# LEDpaideng.net
KiCad netlist of a schematic drawn in EasyEDA Pro
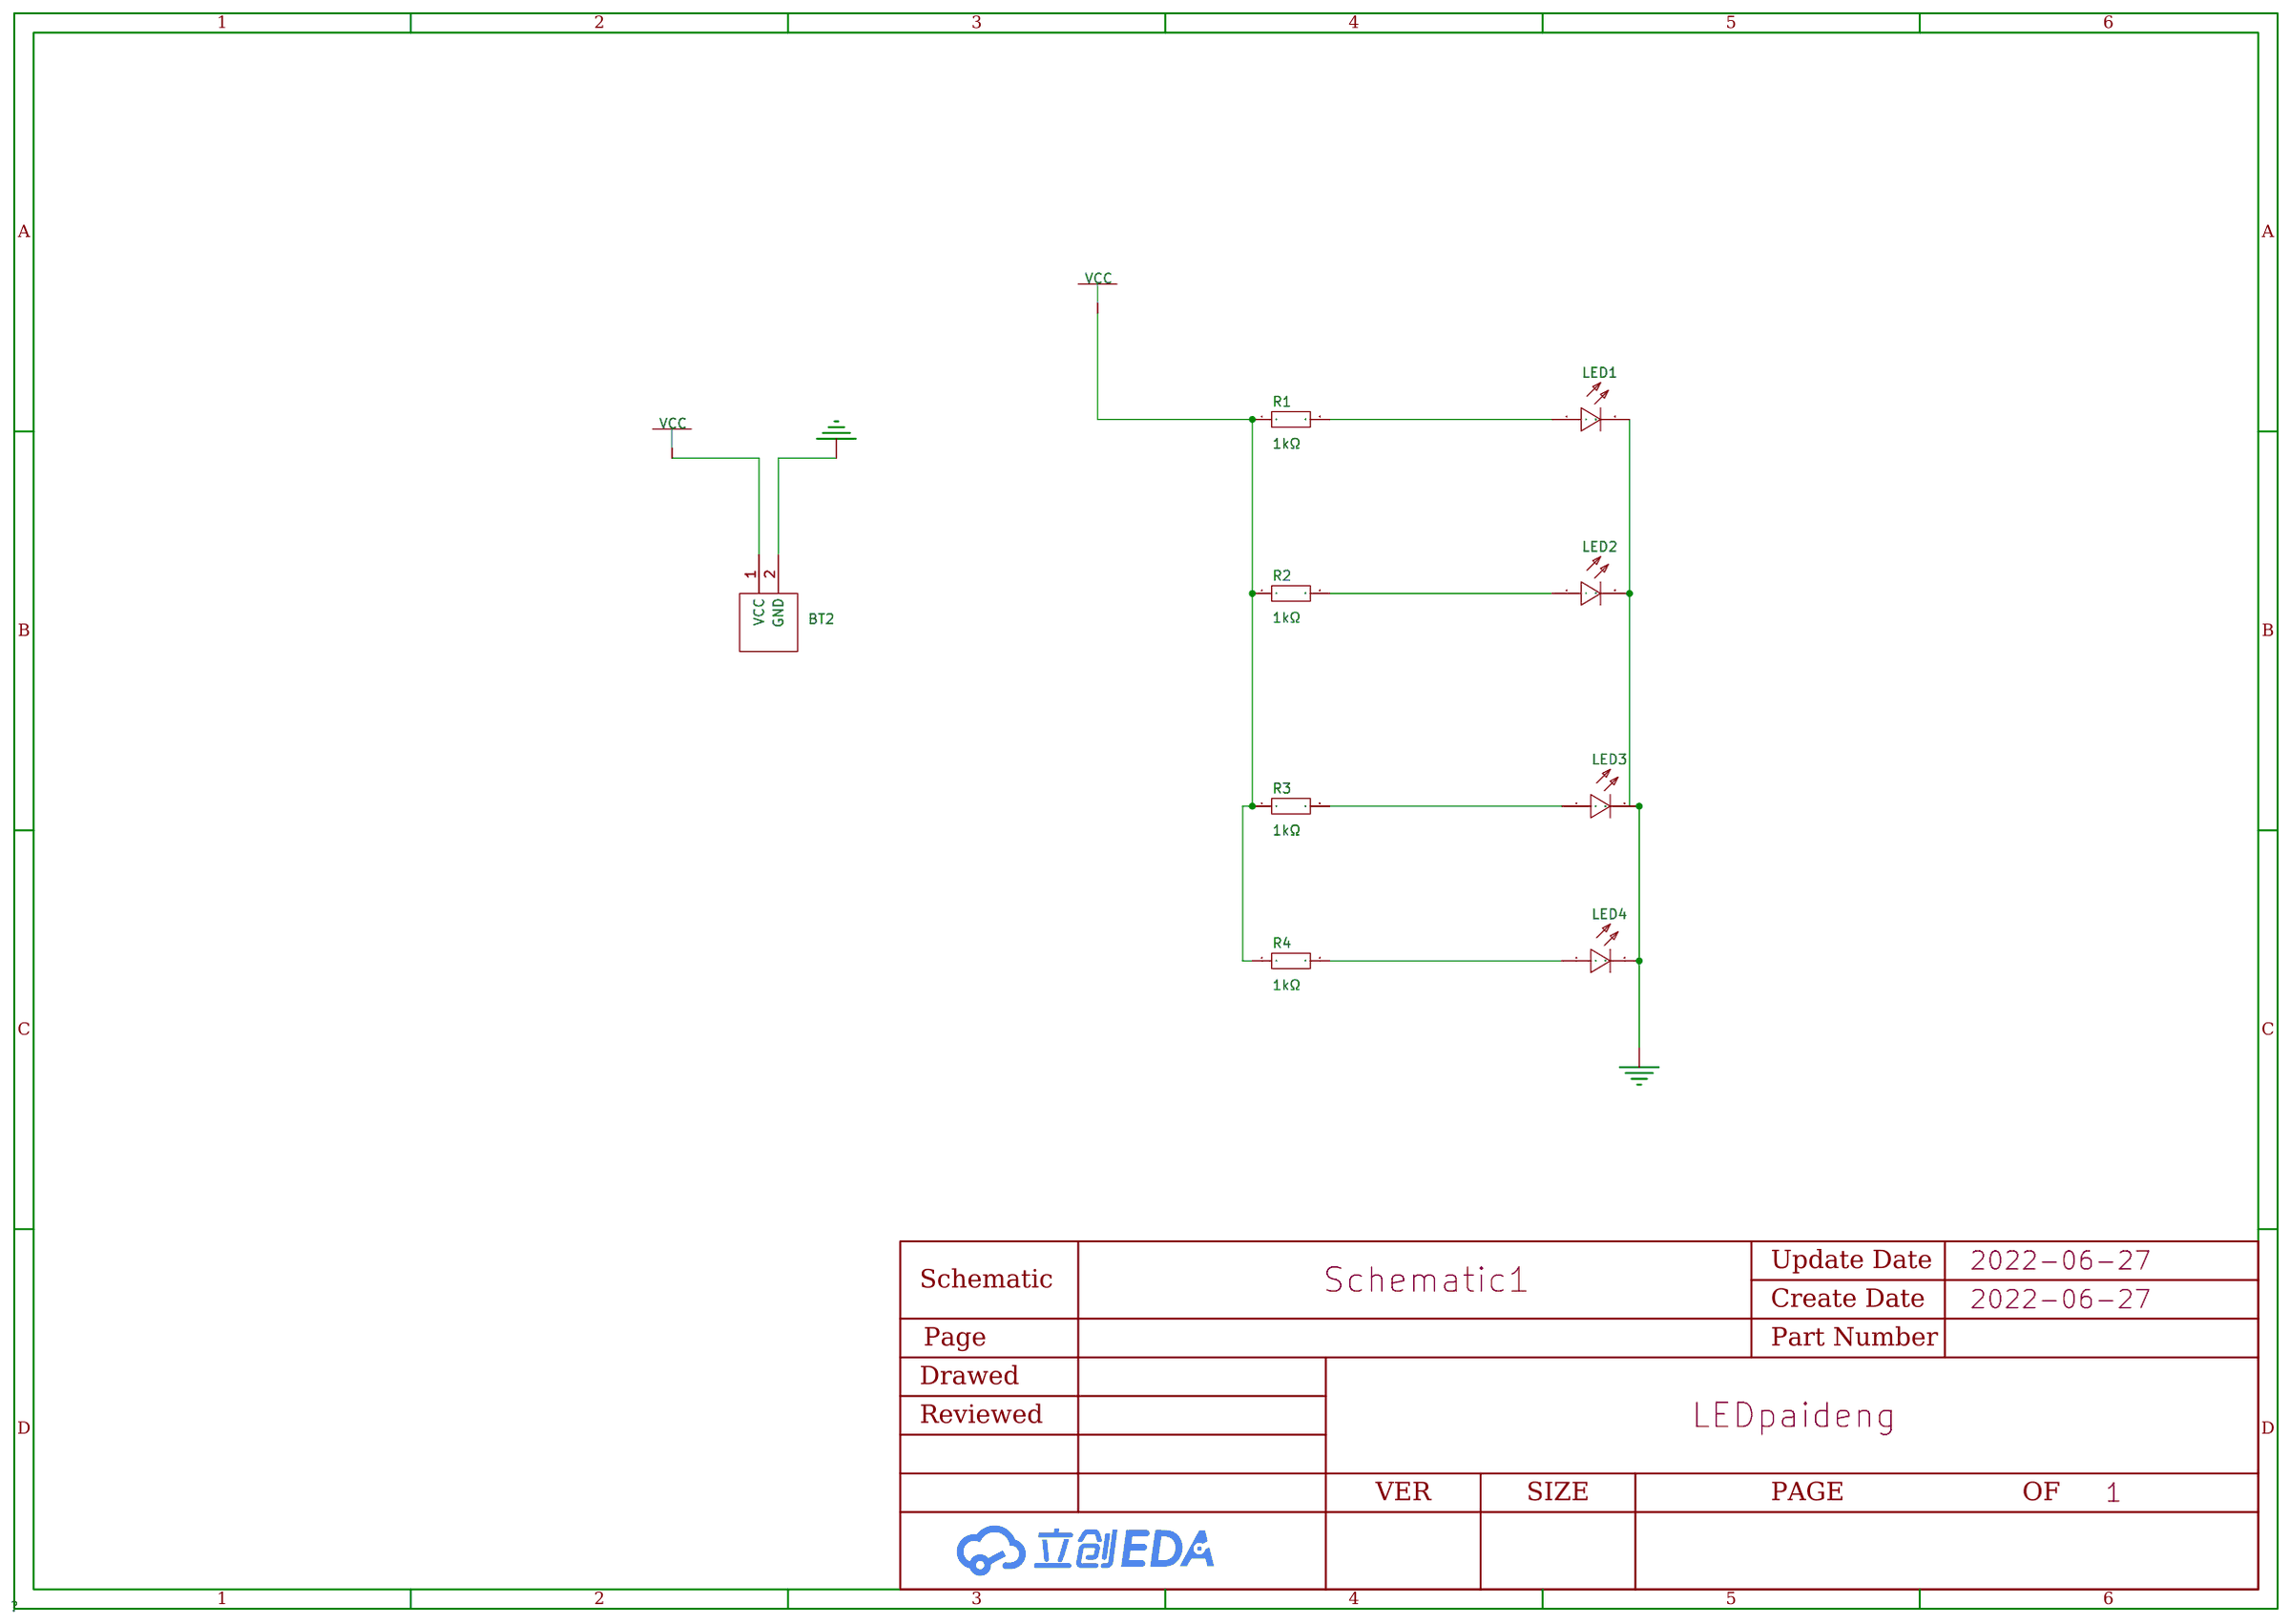
[diagram p0: schematic sheet]

(export (version "E")
  (design (tool "Eeschema 10.0.6"))
  (components
    (comp (ref "BT2")
      (value "~")
      (description "连接器类型:电池盒;适用电池规格:5号;工作温度范围:-;")
      (fields (field (name "Manufacturer Part") "五号2节并列电池盒") (field (name "Manufacturer") "国产"))
      (libsource (lib "easyedapro") (part "No.52Section side by side battery box"))
    )
    (comp (ref "LED1")
      (value "~")
      (footprint "easyedapro:LED0603-R-RD")
      (fields
        (field (name "Manufacturer Part") "19-217/GHC-YR1S2/3T")
        (field (name "Manufacturer") "EVERLIGHT(台湾亿光)")
      )
      (libsource (lib "easyedapro") (part "19-217/GHC-YR1S2/3T"))
    )
    (comp (ref "LED2")
      (value "~")
      (footprint "easyedapro:LED0603-R-RD")
      (fields
        (field (name "Manufacturer Part") "19-217/GHC-YR1S2/3T")
        (field (name "Manufacturer") "EVERLIGHT(台湾亿光)")
      )
      (libsource (lib "easyedapro") (part "19-217/GHC-YR1S2/3T"))
    )
    (comp (ref "LED3")
      (value "~")
      (footprint "easyedapro:LED0603-R-RD")
      (fields
        (field (name "Manufacturer Part") "19-217/GHC-YR1S2/3T")
        (field (name "Manufacturer") "EVERLIGHT(台湾亿光)")
      )
      (libsource (lib "easyedapro") (part "19-217/GHC-YR1S2/3T"))
    )
    (comp (ref "LED4")
      (value "~")
      (footprint "easyedapro:LED0603-R-RD")
      (fields
        (field (name "Manufacturer Part") "19-217/GHC-YR1S2/3T")
        (field (name "Manufacturer") "EVERLIGHT(台湾亿光)")
      )
      (libsource (lib "easyedapro") (part "19-217/GHC-YR1S2/3T"))
    )
    (comp (ref "R1")
      (value "1kΩ")
      (footprint "easyedapro:R0201")
      (description "阻值:10kΩ;精度:±1%;功率:50mW;温度系数:±200ppm/;最大工作电压:25V;工作温度范围:-55~+125;")
      (fields (field (name "Manufacturer Part") "RC-01W1002FT") (field (name "Manufacturer") "FH(风华)"))
      (libsource (lib "easyedapro") (part "RC-01W1002FT"))
    )
    (comp (ref "R2")
      (value "1kΩ")
      (footprint "easyedapro:R0201")
      (description "阻值:10kΩ;精度:±1%;功率:50mW;温度系数:±200ppm/;最大工作电压:25V;工作温度范围:-55~+125;")
      (fields (field (name "Manufacturer Part") "RC-01W1002FT") (field (name "Manufacturer") "FH(风华)"))
      (libsource (lib "easyedapro") (part "RC-01W1002FT"))
    )
    (comp (ref "R3")
      (value "1kΩ")
      (footprint "easyedapro:R0201")
      (description "阻值:10kΩ;精度:±1%;功率:50mW;温度系数:±200ppm/;最大工作电压:25V;工作温度范围:-55~+125;")
      (fields (field (name "Manufacturer Part") "RC-01W1002FT") (field (name "Manufacturer") "FH(风华)"))
      (libsource (lib "easyedapro") (part "RC-01W1002FT"))
    )
    (comp (ref "R4")
      (value "1kΩ")
      (footprint "easyedapro:R0201")
      (description "阻值:10kΩ;精度:±1%;功率:50mW;温度系数:±200ppm/;最大工作电压:25V;工作温度范围:-55~+125;")
      (fields (field (name "Manufacturer Part") "RC-01W1002FT") (field (name "Manufacturer") "FH(风华)"))
      (libsource (lib "easyedapro") (part "RC-01W1002FT"))
    )
  )
  (nets
    (net (code "1") (name "GND") (class "Default")
      (node (ref "BT2") (pin "2") (pinfunction "GND_2") (pintype "input"))
      (node (ref "LED1") (pin "2") (pinfunction "C_2") (pintype "input"))
      (node (ref "LED2") (pin "2") (pinfunction "C_2") (pintype "input"))
      (node (ref "LED3") (pin "2") (pinfunction "C_2") (pintype "input"))
      (node (ref "LED4") (pin "2") (pinfunction "C_2") (pintype "input"))
    )
    (net (code "2") (name "Net-(LED1-A)") (class "Default")
      (node (ref "LED1") (pin "1") (pinfunction "A_1") (pintype "input"))
      (node (ref "R1") (pin "2") (pinfunction "2_2") (pintype "input"))
    )
    (net (code "3") (name "Net-(LED2-A)") (class "Default")
      (node (ref "LED2") (pin "1") (pinfunction "A_1") (pintype "input"))
      (node (ref "R2") (pin "2") (pinfunction "2_2") (pintype "input"))
    )
    (net (code "4") (name "Net-(LED3-A)") (class "Default")
      (node (ref "LED3") (pin "1") (pinfunction "A_1") (pintype "input"))
      (node (ref "R3") (pin "2") (pinfunction "2_2") (pintype "input"))
    )
    (net (code "5") (name "Net-(LED4-A)") (class "Default")
      (node (ref "LED4") (pin "1") (pinfunction "A_1") (pintype "input"))
      (node (ref "R4") (pin "2") (pinfunction "2_2") (pintype "input"))
    )
    (net (code "6") (name "VCC") (class "Default")
      (node (ref "BT2") (pin "1") (pinfunction "VCC_1") (pintype "input"))
      (node (ref "R1") (pin "1") (pinfunction "1_1") (pintype "input"))
      (node (ref "R2") (pin "1") (pinfunction "1_1") (pintype "input"))
      (node (ref "R3") (pin "1") (pinfunction "1_1") (pintype "input"))
      (node (ref "R4") (pin "1") (pinfunction "1_1") (pintype "input"))
    )
  )
)
